# 11_LedDon.net
KiCad netlist of a schematic drawn in Altium Designer
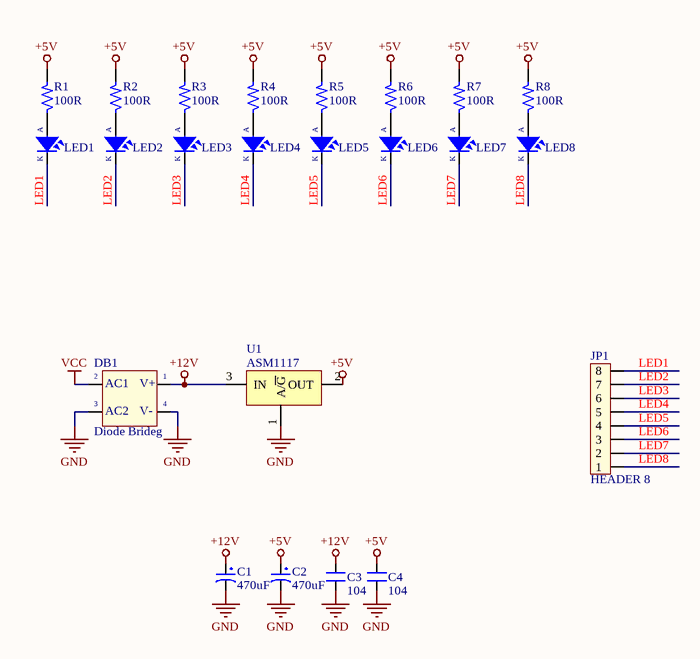
[diagram p0: 11. LedDon.SchDoc]

(export (version "E")
  (design (tool "Eeschema 10.0.6"))
  (components
    (comp (ref "C1")
      (value "470uF")
      (footprint "C-ALU-D6.5")
      (description "Cap P  0,1uF < 22uF , 16 - 50V")
      (libsource (lib "PART") (part "CP1"))
    )
    (comp (ref "C2")
      (value "470uF")
      (footprint "C-ALU-D6.5")
      (description "Cap P  0,1uF < 22uF , 16 - 50V")
      (libsource (lib "PART") (part "CP1"))
    )
    (comp (ref "C3")
      (value "104")
      (footprint "C-0805")
      (fields (field (name "DESIGNED BY") "VanDungEvn"))
      (libsource (lib "syhaunguyen") (part "CN"))
    )
    (comp (ref "C4")
      (value "104")
      (footprint "C-0805")
      (fields (field (name "DESIGNED BY") "VanDungEvn"))
      (libsource (lib "syhaunguyen") (part "CN"))
    )
    (comp (ref "DB1")
      (value "Diode Brideg")
      (footprint "D-DB-1A-SMD")
      (description "Convert AC to DC voltage, 4 pin")
      (libsource (lib "PART") (part "DB"))
    )
    (comp (ref "JP1")
      (value "HEADER 8")
      (footprint "JP8-2.54")
      (description "JP8 PIN")
      (libsource (lib "PART") (part "JP8"))
    )
    (comp (ref "LED1")
      (value "LED")
      (footprint "LED-D3")
      (description "LED Single colour Green and Red")
      (libsource (lib "PART") (part "LED"))
    )
    (comp (ref "LED2")
      (value "LED")
      (footprint "LED-D3")
      (description "LED Single colour Green and Red")
      (libsource (lib "PART") (part "LED"))
    )
    (comp (ref "LED3")
      (value "LED")
      (footprint "LED-D3")
      (description "LED Single colour Green and Red")
      (libsource (lib "PART") (part "LED"))
    )
    (comp (ref "LED4")
      (value "LED")
      (footprint "LED-D3")
      (description "LED Single colour Green and Red")
      (libsource (lib "PART") (part "LED"))
    )
    (comp (ref "LED5")
      (value "LED")
      (footprint "LED-D3")
      (description "LED Single colour Green and Red")
      (libsource (lib "PART") (part "LED"))
    )
    (comp (ref "LED6")
      (value "LED")
      (footprint "LED-D3")
      (description "LED Single colour Green and Red")
      (libsource (lib "PART") (part "LED"))
    )
    (comp (ref "LED7")
      (value "LED")
      (footprint "LED-D3")
      (description "LED Single colour Green and Red")
      (libsource (lib "PART") (part "LED"))
    )
    (comp (ref "LED8")
      (value "LED")
      (footprint "LED-D3")
      (description "LED Single colour Green and Red")
      (libsource (lib "PART") (part "LED"))
    )
    (comp (ref "R1")
      (value "100R")
      (footprint "R-0805")
      (description "Resistor 1/4W")
      (libsource (lib "PART") (part "R"))
    )
    (comp (ref "R2")
      (value "100R")
      (footprint "R-0805")
      (description "Resistor 1/4W")
      (libsource (lib "PART") (part "R"))
    )
    (comp (ref "R3")
      (value "100R")
      (footprint "R-0805")
      (description "Resistor 1/4W")
      (libsource (lib "PART") (part "R"))
    )
    (comp (ref "R4")
      (value "100R")
      (footprint "R-0805")
      (description "Resistor 1/4W")
      (libsource (lib "PART") (part "R"))
    )
    (comp (ref "R5")
      (value "100R")
      (footprint "R-0805")
      (description "Resistor 1/4W")
      (libsource (lib "PART") (part "R"))
    )
    (comp (ref "R6")
      (value "100R")
      (footprint "R-0805")
      (description "Resistor 1/4W")
      (libsource (lib "PART") (part "R"))
    )
    (comp (ref "R7")
      (value "100R")
      (footprint "R-0805")
      (description "Resistor 1/4W")
      (libsource (lib "PART") (part "R"))
    )
    (comp (ref "R8")
      (value "100R")
      (footprint "R-0805")
      (description "Resistor 1/4W")
      (libsource (lib "PART") (part "R"))
    )
    (comp (ref "U1")
      (value "ASM1117")
      (footprint "TO-252")
      (libsource (lib "doAnTotNghiep2017Lib") (part "ASM1117"))
    )
  )
  (nets
    (net (code "1") (name "+5V") (class "Default")
      (node (ref "C2") (pin "1") (pinfunction "1_1") (pintype "passive"))
      (node (ref "C4") (pin "2") (pinfunction "2_2") (pintype "passive"))
      (node (ref "R1") (pin "2") (pinfunction "2_2") (pintype "passive"))
      (node (ref "R2") (pin "2") (pinfunction "2_2") (pintype "passive"))
      (node (ref "R3") (pin "2") (pinfunction "2_2") (pintype "passive"))
      (node (ref "R4") (pin "2") (pinfunction "2_2") (pintype "passive"))
      (node (ref "R5") (pin "2") (pinfunction "2_2") (pintype "passive"))
      (node (ref "R6") (pin "2") (pinfunction "2_2") (pintype "passive"))
      (node (ref "R7") (pin "2") (pinfunction "2_2") (pintype "passive"))
      (node (ref "R8") (pin "2") (pinfunction "2_2") (pintype "passive"))
      (node (ref "U1") (pin "2") (pinfunction "OUT_2") (pintype "passive"))
    )
    (net (code "2") (name "+12V") (class "Default")
      (node (ref "C1") (pin "1") (pinfunction "1_1") (pintype "passive"))
      (node (ref "C3") (pin "2") (pinfunction "2_2") (pintype "passive"))
      (node (ref "DB1") (pin "3") (pinfunction "AC2_3") (pintype "passive"))
      (node (ref "U1") (pin "3") (pinfunction "IN_3") (pintype "passive"))
    )
    (net (code "3") (name "/LED1") (class "Default")
      (node (ref "JP1") (pin "8") (pinfunction "8_8") (pintype "passive"))
      (node (ref "LED1") (pin "2") (pinfunction "K_2") (pintype "passive"))
    )
    (net (code "4") (name "/LED2") (class "Default")
      (node (ref "JP1") (pin "7") (pinfunction "7_7") (pintype "passive"))
      (node (ref "LED2") (pin "2") (pinfunction "K_2") (pintype "passive"))
    )
    (net (code "5") (name "/LED3") (class "Default")
      (node (ref "JP1") (pin "6") (pinfunction "6_6") (pintype "passive"))
      (node (ref "LED3") (pin "2") (pinfunction "K_2") (pintype "passive"))
    )
    (net (code "6") (name "/LED4") (class "Default")
      (node (ref "JP1") (pin "5") (pinfunction "5_5") (pintype "passive"))
      (node (ref "LED4") (pin "2") (pinfunction "K_2") (pintype "passive"))
    )
    (net (code "7") (name "/LED5") (class "Default")
      (node (ref "JP1") (pin "4") (pinfunction "4_4") (pintype "passive"))
      (node (ref "LED5") (pin "2") (pinfunction "K_2") (pintype "passive"))
    )
    (net (code "8") (name "/LED6") (class "Default")
      (node (ref "JP1") (pin "3") (pinfunction "3_3") (pintype "passive"))
      (node (ref "LED6") (pin "2") (pinfunction "K_2") (pintype "passive"))
    )
    (net (code "9") (name "/LED7") (class "Default")
      (node (ref "JP1") (pin "2") (pinfunction "2_2") (pintype "passive"))
      (node (ref "LED7") (pin "2") (pinfunction "K_2") (pintype "passive"))
    )
    (net (code "10") (name "/LED8") (class "Default")
      (node (ref "JP1") (pin "1") (pinfunction "1_1") (pintype "passive"))
      (node (ref "LED8") (pin "2") (pinfunction "K_2") (pintype "passive"))
    )
    (net (code "11") (name "GND") (class "Default")
      (node (ref "C1") (pin "2") (pinfunction "2_2") (pintype "passive"))
      (node (ref "C2") (pin "2") (pinfunction "2_2") (pintype "passive"))
      (node (ref "C3") (pin "1") (pinfunction "1_1") (pintype "passive"))
      (node (ref "C4") (pin "1") (pinfunction "1_1") (pintype "passive"))
      (node (ref "DB1") (pin "1") (pinfunction "+V_OUT_1") (pintype "passive"))
      (node (ref "DB1") (pin "4") (pinfunction "-V_OUT_4") (pintype "passive"))
      (node (ref "U1") (pin "1") (pinfunction "A/~{G}_1") (pintype "passive"))
    )
    (net (code "12") (name "Net-(LED1-A)") (class "Default")
      (node (ref "LED1") (pin "1") (pinfunction "A_1") (pintype "passive"))
      (node (ref "R1") (pin "1") (pinfunction "1_1") (pintype "passive"))
    )
    (net (code "13") (name "Net-(LED2-A)") (class "Default")
      (node (ref "LED2") (pin "1") (pinfunction "A_1") (pintype "passive"))
      (node (ref "R2") (pin "1") (pinfunction "1_1") (pintype "passive"))
    )
    (net (code "14") (name "Net-(LED3-A)") (class "Default")
      (node (ref "LED3") (pin "1") (pinfunction "A_1") (pintype "passive"))
      (node (ref "R3") (pin "1") (pinfunction "1_1") (pintype "passive"))
    )
    (net (code "15") (name "Net-(LED4-A)") (class "Default")
      (node (ref "LED4") (pin "1") (pinfunction "A_1") (pintype "passive"))
      (node (ref "R4") (pin "1") (pinfunction "1_1") (pintype "passive"))
    )
    (net (code "16") (name "Net-(LED5-A)") (class "Default")
      (node (ref "LED5") (pin "1") (pinfunction "A_1") (pintype "passive"))
      (node (ref "R5") (pin "1") (pinfunction "1_1") (pintype "passive"))
    )
    (net (code "17") (name "Net-(LED6-A)") (class "Default")
      (node (ref "LED6") (pin "1") (pinfunction "A_1") (pintype "passive"))
      (node (ref "R6") (pin "1") (pinfunction "1_1") (pintype "passive"))
    )
    (net (code "18") (name "Net-(LED7-A)") (class "Default")
      (node (ref "LED7") (pin "1") (pinfunction "A_1") (pintype "passive"))
      (node (ref "R7") (pin "1") (pinfunction "1_1") (pintype "passive"))
    )
    (net (code "19") (name "Net-(LED8-A)") (class "Default")
      (node (ref "LED8") (pin "1") (pinfunction "A_1") (pintype "passive"))
      (node (ref "R8") (pin "1") (pinfunction "1_1") (pintype "passive"))
    )
    (net (code "20") (name "VCC") (class "Default")
      (node (ref "DB1") (pin "2") (pinfunction "AC1_2") (pintype "passive"))
    )
  )
)
